# UTN-ESEXT01.net
KiCad netlist of a schematic drawn in EAGLE
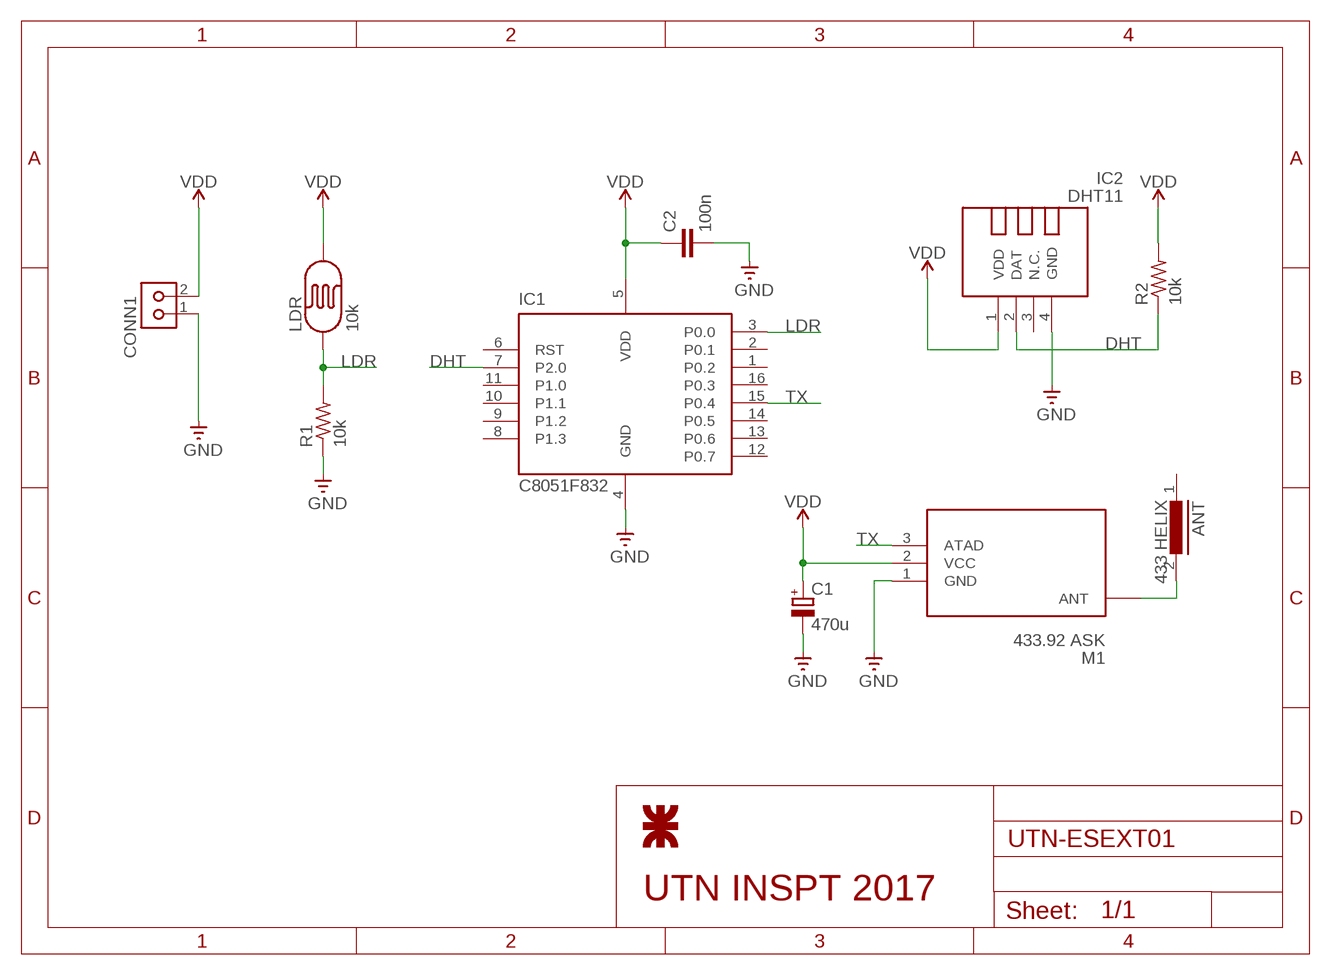
[diagram p0: schematic, sheet 1]

(export (version "E")
  (design (tool "Eeschema 10.0.6"))
  (components
    (comp (ref "ANT")
      (value "433 HELIX")
      (footprint "eagle-import:SMSC20")
      (libsource (lib "eagle-import") (part "SMSC20"))
    )
    (comp (ref "C1")
      (value "470u")
      (footprint "eagle-import:E3,5-10")
      (libsource (lib "eagle-import") (part "CPOL-EUE3.5-10"))
    )
    (comp (ref "C2")
      (value "100n")
      (footprint "eagle-import:C050-024X044")
      (libsource (lib "eagle-import") (part "C-EU050-024X044"))
    )
    (comp (ref "CONN1")
      (value "KK2VSQ")
      (footprint "eagle-import:KK-V-2-SQ")
      (libsource (lib "eagle-import") (part "KK2VSQ"))
    )
    (comp (ref "IC1")
      (value "C8051F832")
      (footprint "eagle-import:SOIC16R")
      (libsource (lib "eagle-import") (part "C8051F832"))
    )
    (comp (ref "IC2")
      (value "DHT11")
      (footprint "eagle-import:TEMP-HUM-SENSOR-DHT11")
      (libsource (lib "eagle-import") (part "TEMP-HUM-SENSOR-DHT11"))
    )
    (comp (ref "LDR")
      (value "10k")
      (footprint "eagle-import:ON_BOARD")
      (libsource (lib "eagle-import") (part "PHOTOCELLONB"))
    )
    (comp (ref "M1")
      (value "433.92 ASK")
      (footprint "eagle-import:WIRELESS-XY-FST")
      (libsource (lib "eagle-import") (part "WIRELESS-XY-FST"))
    )
    (comp (ref "R1")
      (value "10k")
      (footprint "eagle-import:0207_10")
      (libsource (lib "eagle-import") (part "R-US_0207/10"))
    )
    (comp (ref "R2")
      (value "10k")
      (footprint "eagle-import:0207_10")
      (libsource (lib "eagle-import") (part "R-US_0207/10"))
    )
    (comp (ref "U$3")
      (value "UTN_LOGO")
      (footprint "eagle-import:UTN_LOGO")
      (libsource (lib "eagle-import") (part "UTN_LOGO"))
    )
  )
  (nets
    (net (code "1") (name "/DHT") (class "Default")
      (node (ref "IC1") (pin "7") (pinfunction "P2.0_7") (pintype "bidirectional"))
      (node (ref "IC2") (pin "2") (pinfunction "DAT_2") (pintype "bidirectional"))
      (node (ref "R2") (pin "1") (pinfunction "1_1") (pintype "passive"))
    )
    (net (code "2") (name "/LDR") (class "Default")
      (node (ref "IC1") (pin "3") (pinfunction "P0.0_3") (pintype "bidirectional"))
      (node (ref "LDR") (pin "1") (pinfunction "P$1_1") (pintype "bidirectional"))
      (node (ref "R1") (pin "2") (pinfunction "2_2") (pintype "passive"))
    )
    (net (code "3") (name "/TX") (class "Default")
      (node (ref "IC1") (pin "15") (pinfunction "P0.4_15") (pintype "bidirectional"))
      (node (ref "M1") (pin "3") (pinfunction "ATAD_3") (pintype "input"))
    )
    (net (code "4") (name "GND") (class "Default")
      (node (ref "C1") (pin "-") (pinfunction "-_-") (pintype "passive"))
      (node (ref "C2") (pin "2") (pinfunction "2_2") (pintype "passive"))
      (node (ref "CONN1") (pin "1") (pinfunction "1_1") (pintype "bidirectional"))
      (node (ref "IC1") (pin "4") (pinfunction "GND_4") (pintype "bidirectional"))
      (node (ref "IC2") (pin "4") (pinfunction "GND_4") (pintype "power_in"))
      (node (ref "M1") (pin "1") (pinfunction "GND_1") (pintype "power_in"))
      (node (ref "R1") (pin "1") (pinfunction "1_1") (pintype "passive"))
    )
    (net (code "5") (name "Net-(ANT-Pad2)") (class "Default")
      (node (ref "ANT") (pin "2") (pinfunction "2_2") (pintype "passive"))
      (node (ref "M1") (pin "ANT") (pinfunction "ANT_ANT") (pintype "output"))
    )
    (net (code "6") (name "VDD") (class "Default")
      (node (ref "C1") (pin "+") (pinfunction "+_+") (pintype "passive"))
      (node (ref "C2") (pin "1") (pinfunction "1_1") (pintype "passive"))
      (node (ref "CONN1") (pin "2") (pinfunction "2_2") (pintype "bidirectional"))
      (node (ref "IC1") (pin "5") (pinfunction "VDD_5") (pintype "bidirectional"))
      (node (ref "IC2") (pin "1") (pinfunction "VDD_1") (pintype "power_in"))
      (node (ref "LDR") (pin "2") (pinfunction "P$2_2") (pintype "bidirectional"))
      (node (ref "M1") (pin "2") (pinfunction "VCC_2") (pintype "power_in"))
      (node (ref "R2") (pin "2") (pinfunction "2_2") (pintype "passive"))
    )
    (net (code "7") (name "unconnected-(ANT-Pad1)") (class "Default")
      (node (ref "ANT") (pin "1") (pinfunction "1_1") (pintype "passive"))
    )
    (net (code "8") (name "unconnected-(IC1-P0.1-Pad2)") (class "Default")
      (node (ref "IC1") (pin "2") (pinfunction "P0.1_2") (pintype "bidirectional"))
    )
    (net (code "9") (name "unconnected-(IC1-P0.2-Pad1)") (class "Default")
      (node (ref "IC1") (pin "1") (pinfunction "P0.2_1") (pintype "bidirectional"))
    )
    (net (code "10") (name "unconnected-(IC1-P0.3-Pad16)") (class "Default")
      (node (ref "IC1") (pin "16") (pinfunction "P0.3_16") (pintype "bidirectional"))
    )
    (net (code "11") (name "unconnected-(IC1-P0.5-Pad14)") (class "Default")
      (node (ref "IC1") (pin "14") (pinfunction "P0.5_14") (pintype "bidirectional"))
    )
    (net (code "12") (name "unconnected-(IC1-P0.6-Pad13)") (class "Default")
      (node (ref "IC1") (pin "13") (pinfunction "P0.6_13") (pintype "bidirectional"))
    )
    (net (code "13") (name "unconnected-(IC1-P0.7-Pad12)") (class "Default")
      (node (ref "IC1") (pin "12") (pinfunction "P0.7_12") (pintype "bidirectional"))
    )
    (net (code "14") (name "unconnected-(IC1-P1.0-Pad11)") (class "Default")
      (node (ref "IC1") (pin "11") (pinfunction "P1.0_11") (pintype "bidirectional"))
    )
    (net (code "15") (name "unconnected-(IC1-P1.1-Pad10)") (class "Default")
      (node (ref "IC1") (pin "10") (pinfunction "P1.1_10") (pintype "bidirectional"))
    )
    (net (code "16") (name "unconnected-(IC1-P1.2-Pad9)") (class "Default")
      (node (ref "IC1") (pin "9") (pinfunction "P1.2_9") (pintype "bidirectional"))
    )
    (net (code "17") (name "unconnected-(IC1-P1.3-Pad8)") (class "Default")
      (node (ref "IC1") (pin "8") (pinfunction "P1.3_8") (pintype "bidirectional"))
    )
    (net (code "18") (name "unconnected-(IC1-RST-Pad6)") (class "Default")
      (node (ref "IC1") (pin "6") (pinfunction "RST_6") (pintype "bidirectional"))
    )
    (net (code "19") (name "unconnected-(IC2-N.C.-Pad3)") (class "Default")
      (node (ref "IC2") (pin "3") (pinfunction "N.C._3") (pintype "passive"))
    )
  )
)
